# EtherIOv2.net
KiCad netlist of a schematic drawn in Altium Designer
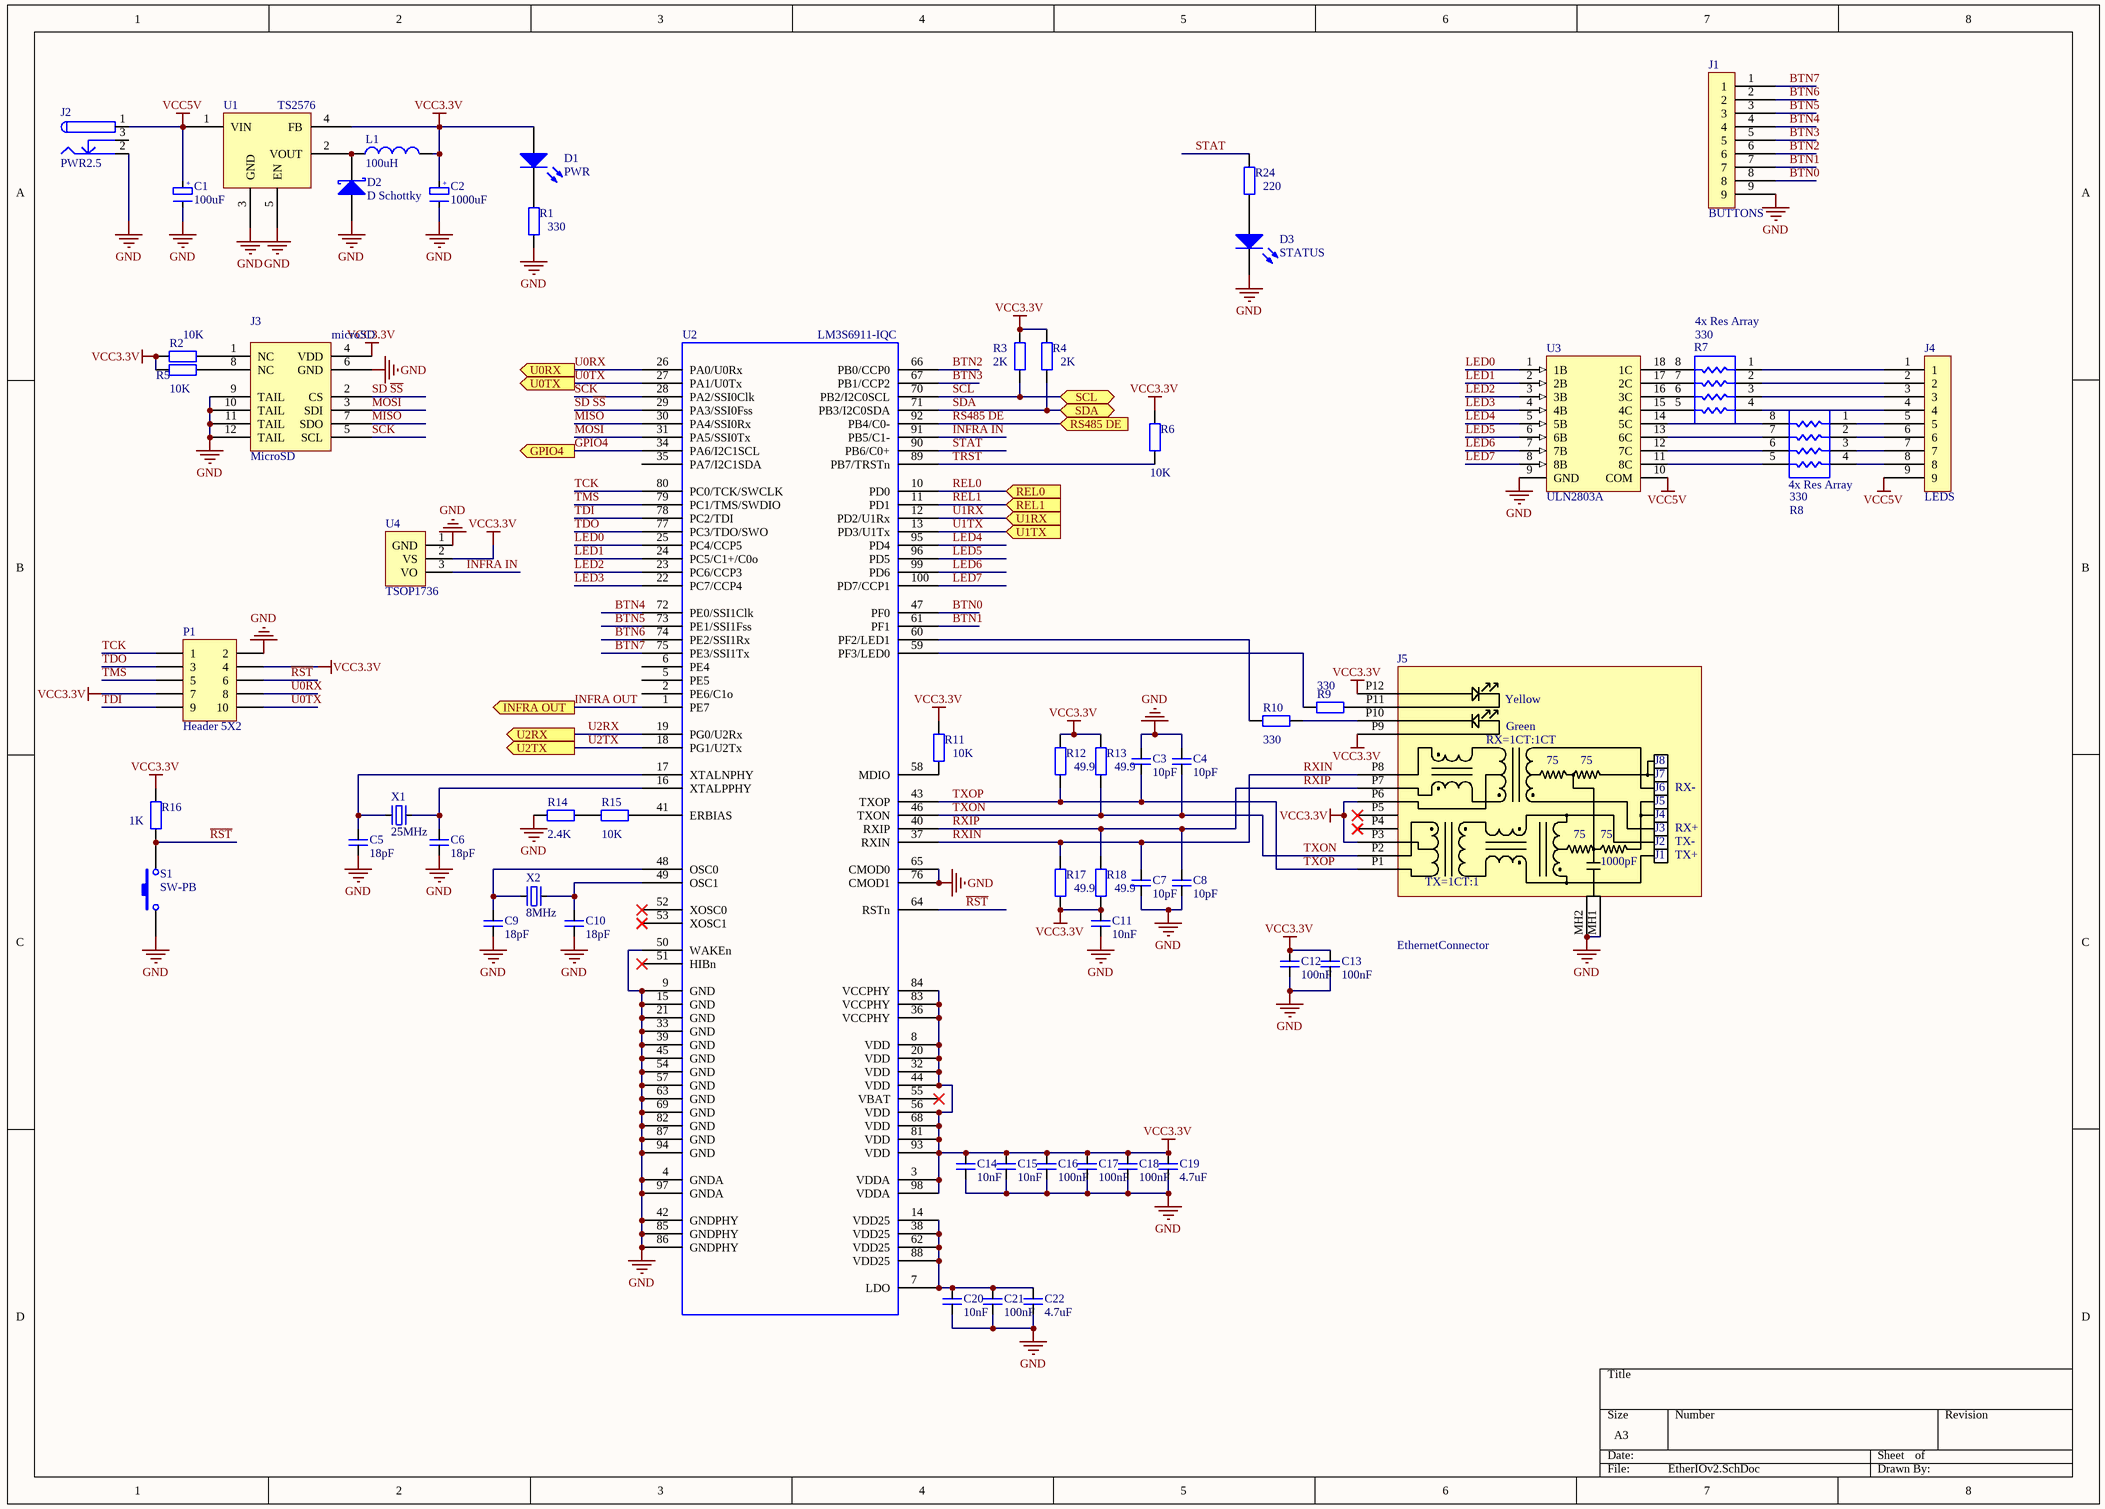
[diagram p0: EtherIOv2.SchDoc]

(export (version "E")
  (design (tool "Eeschema 10.0.6"))
  (components
    (comp (ref "C1")
      (value "100uF")
      (footprint "Electrolit Cap F80")
      (description "SMD Electrolit Capacitor")
      (fields (field (name "Comment") "100uF_25V"))
      (libsource (lib "EtherIOv2") (part "100uF_25V"))
    )
    (comp (ref "C2")
      (value "1000uF")
      (footprint "Electrolit Cap J10")
      (description "SMD Electrolit Capacitor")
      (fields (field (name "Comment") "1000uF_6V3"))
      (libsource (lib "EtherIOv2") (part "1000uF_6V3"))
    )
    (comp (ref "C3")
      (value "10pF")
      (footprint "0805 CAP")
      (description "Capacitor")
      (fields (field (name "Comment") "CAP"))
      (libsource (lib "EtherIOv2") (part "CAP"))
    )
    (comp (ref "C4")
      (value "10pF")
      (footprint "0805 CAP")
      (description "Capacitor")
      (fields (field (name "Comment") "CAP"))
      (libsource (lib "EtherIOv2") (part "CAP"))
    )
    (comp (ref "C5")
      (value "18pF")
      (footprint "0805 CAP")
      (description "Capacitor")
      (fields (field (name "Comment") "CAP"))
      (libsource (lib "EtherIOv2") (part "CAP"))
    )
    (comp (ref "C6")
      (value "18pF")
      (footprint "0805 CAP")
      (description "Capacitor")
      (fields (field (name "Comment") "CAP"))
      (libsource (lib "EtherIOv2") (part "CAP"))
    )
    (comp (ref "C7")
      (value "10pF")
      (footprint "0805 CAP")
      (description "Capacitor")
      (fields (field (name "Comment") "CAP"))
      (libsource (lib "EtherIOv2") (part "CAP"))
    )
    (comp (ref "C8")
      (value "10pF")
      (footprint "0805 CAP")
      (description "Capacitor")
      (fields (field (name "Comment") "CAP"))
      (libsource (lib "EtherIOv2") (part "CAP"))
    )
    (comp (ref "C9")
      (value "18pF")
      (footprint "0805 CAP")
      (description "Capacitor")
      (fields (field (name "Comment") "CAP"))
      (libsource (lib "EtherIOv2") (part "CAP"))
    )
    (comp (ref "C10")
      (value "18pF")
      (footprint "0805 CAP")
      (description "Capacitor")
      (fields (field (name "Comment") "CAP"))
      (libsource (lib "EtherIOv2") (part "CAP"))
    )
    (comp (ref "C11")
      (value "10nF")
      (footprint "0805 CAP")
      (description "Capacitor")
      (fields (field (name "Comment") "CAP"))
      (libsource (lib "EtherIOv2") (part "CAP"))
    )
    (comp (ref "C12")
      (value "100nF")
      (footprint "0805 CAP")
      (description "Capacitor")
      (fields (field (name "Comment") "CAP"))
      (libsource (lib "EtherIOv2") (part "CAP"))
    )
    (comp (ref "C13")
      (value "100nF")
      (footprint "0805 CAP")
      (description "Capacitor")
      (fields (field (name "Comment") "CAP"))
      (libsource (lib "EtherIOv2") (part "CAP"))
    )
    (comp (ref "C14")
      (value "10nF")
      (footprint "0805 CAP")
      (description "Capacitor")
      (fields (field (name "Comment") "CAP"))
      (libsource (lib "EtherIOv2") (part "CAP"))
    )
    (comp (ref "C15")
      (value "10nF")
      (footprint "0805 CAP")
      (description "Capacitor")
      (fields (field (name "Comment") "CAP"))
      (libsource (lib "EtherIOv2") (part "CAP"))
    )
    (comp (ref "C16")
      (value "100nF")
      (footprint "0805 CAP")
      (description "Capacitor")
      (fields (field (name "Comment") "CAP"))
      (libsource (lib "EtherIOv2") (part "CAP"))
    )
    (comp (ref "C17")
      (value "100nF")
      (footprint "0805 CAP")
      (description "Capacitor")
      (fields (field (name "Comment") "CAP"))
      (libsource (lib "EtherIOv2") (part "CAP"))
    )
    (comp (ref "C18")
      (value "100nF")
      (footprint "0805 CAP")
      (description "Capacitor")
      (fields (field (name "Comment") "CAP"))
      (libsource (lib "EtherIOv2") (part "CAP"))
    )
    (comp (ref "C19")
      (value "4.7uF")
      (footprint "0805 CAP")
      (description "Capacitor")
      (fields (field (name "Comment") "CAP"))
      (libsource (lib "EtherIOv2") (part "CAP"))
    )
    (comp (ref "C20")
      (value "10nF")
      (footprint "0805 CAP")
      (description "Capacitor")
      (fields (field (name "Comment") "CAP"))
      (libsource (lib "EtherIOv2") (part "CAP"))
    )
    (comp (ref "C21")
      (value "100nF")
      (footprint "0805 CAP")
      (description "Capacitor")
      (fields (field (name "Comment") "CAP"))
      (libsource (lib "EtherIOv2") (part "CAP"))
    )
    (comp (ref "C22")
      (value "4.7uF")
      (footprint "0805 CAP")
      (description "Capacitor")
      (fields (field (name "Comment") "CAP"))
      (libsource (lib "EtherIOv2") (part "CAP"))
    )
    (comp (ref "D1")
      (value "PWR")
      (footprint "0805 LED")
      (description "Typical RED, GREEN, YELLOW, AMBER GaAs LED")
      (fields (field (name "PUBLISHER") "Altium Limited"))
      (libsource (lib "Miscellaneous Devices") (part "LED2"))
    )
    (comp (ref "D2")
      (value "D Schottky")
      (footprint "DSO-C2/X2.3")
      (description "Schottky Diode")
      (fields (field (name "PUBLISHER") "Altium Limited"))
      (libsource (lib "Miscellaneous Devices") (part "D Schottky"))
    )
    (comp (ref "D3")
      (value "STATUS")
      (footprint "LED-1")
      (description "Typical RED GaAs LED")
      (fields (field (name "PUBLISHER") "Altium Limited"))
      (libsource (lib "Miscellaneous Devices") (part "LED1"))
    )
    (comp (ref "J1")
      (value "BUTTONS")
      (footprint "Euroblock 3.5pitch 9P")
      (libsource (lib "EtherIOv2") (part "Euroblock 9P connector"))
    )
    (comp (ref "J2")
      (value "PWR2.5")
      (footprint "KLD-0202")
      (description "Low Voltage Power Supply Connector")
      (fields (field (name "PUBLISHER") "Altium Limited"))
      (libsource (lib "EtherIOv2") (part "PWR2.5"))
    )
    (comp (ref "J3") (value "MicroSD") (footprint "microSD") (libsource (lib "Waterstars") (part "MicroSD")))
    (comp (ref "J4")
      (value "LEDS")
      (footprint "Euroblock 3.5pitch 9P")
      (libsource (lib "") (part "Euroblock 9P connector_1"))
    )
    (comp (ref "J5")
      (value "EthernetConnector")
      (footprint "LU1T516-43")
      (libsource (lib "EtherIOv2") (part "EthernetConnector"))
    )
    (comp (ref "L1")
      (value "100uH")
      (footprint "INDP127127X85N")
      (description "Inductor")
      (fields (field (name "PUBLISHER") "Altium Limited"))
      (libsource (lib "Miscellaneous Devices") (part "Inductor"))
    )
    (comp (ref "P1")
      (value "Header 5X2")
      (footprint "IDC2.54-V10D")
      (description "Header, 5-Pin, Dual row")
      (fields (field (name "PUBLISHER") "Altium Limited"))
      (libsource (lib "EtherIOv2") (part "Header 5X2"))
    )
    (comp (ref "R1")
      (value "330")
      (footprint "0805 RES")
      (description "Resistor")
      (fields (field (name "Comment") "RES") (field (name "PUBLISHER") "Altium Limited"))
      (libsource (lib "") (part "RES_1"))
    )
    (comp (ref "R2")
      (value "10K")
      (footprint "0805 RES")
      (description "Resistor")
      (fields (field (name "Comment") "RES") (field (name "PUBLISHER") "Altium Limited"))
      (libsource (lib "") (part "RES_2"))
    )
    (comp (ref "R3")
      (value "2K")
      (footprint "0805 RES")
      (description "Resistor")
      (fields (field (name "Comment") "RES") (field (name "PUBLISHER") "Altium Limited"))
      (libsource (lib "") (part "RES_1"))
    )
    (comp (ref "R4")
      (value "2K")
      (footprint "0805 RES")
      (description "Resistor")
      (fields (field (name "Comment") "RES") (field (name "PUBLISHER") "Altium Limited"))
      (libsource (lib "") (part "RES_1"))
    )
    (comp (ref "R5")
      (value "10K")
      (footprint "0805 RES")
      (description "Resistor")
      (fields (field (name "Comment") "RES") (field (name "PUBLISHER") "Altium Limited"))
      (libsource (lib "") (part "RES_2"))
    )
    (comp (ref "R6")
      (value "10K")
      (footprint "0805 RES")
      (description "Resistor")
      (fields (field (name "Comment") "RES") (field (name "PUBLISHER") "Altium Limited"))
      (libsource (lib "") (part "RES_1"))
    )
    (comp (ref "R7")
      (value "4x Res Array")
      (footprint "1206 4xRES ARRAY")
      (description "Isolated Resistor Network")
      (fields (field (name "ALTIUM_VALUE") "330") (field (name "PUBLISHER") "Altium Limited"))
      (libsource (lib "EtherIOv2") (part "4x Res Array"))
    )
    (comp (ref "R8")
      (value "4x Res Array")
      (footprint "1206 4xRES ARRAY")
      (description "Isolated Resistor Network")
      (fields (field (name "ALTIUM_VALUE") "330") (field (name "PUBLISHER") "Altium Limited"))
      (libsource (lib "EtherIOv2") (part "4x Res Array"))
    )
    (comp (ref "R9")
      (value "330")
      (footprint "0805 RES")
      (description "Resistor")
      (fields (field (name "Comment") "RES") (field (name "PUBLISHER") "Altium Limited"))
      (libsource (lib "") (part "RES_3"))
    )
    (comp (ref "R10")
      (value "330")
      (footprint "0805 RES")
      (description "Resistor")
      (fields (field (name "Comment") "RES") (field (name "PUBLISHER") "Altium Limited"))
      (libsource (lib "") (part "RES_3"))
    )
    (comp (ref "R11")
      (value "10K")
      (footprint "0805 RES")
      (description "Resistor")
      (fields (field (name "Comment") "RES") (field (name "PUBLISHER") "Altium Limited"))
      (libsource (lib "") (part "RES_1"))
    )
    (comp (ref "R12")
      (value "49.9")
      (footprint "0805 RES")
      (description "Resistor")
      (fields (field (name "Comment") "RES") (field (name "PUBLISHER") "Altium Limited"))
      (libsource (lib "") (part "RES_1"))
    )
    (comp (ref "R13")
      (value "49.9")
      (footprint "0805 RES")
      (description "Resistor")
      (fields (field (name "Comment") "RES") (field (name "PUBLISHER") "Altium Limited"))
      (libsource (lib "") (part "RES_1"))
    )
    (comp (ref "R14")
      (value "2.4K")
      (footprint "0805 RES")
      (description "Resistor")
      (fields (field (name "Comment") "RES") (field (name "PUBLISHER") "Altium Limited"))
      (libsource (lib "") (part "RES_3"))
    )
    (comp (ref "R15")
      (value "10K")
      (footprint "0805 RES")
      (description "Resistor")
      (fields (field (name "Comment") "RES") (field (name "PUBLISHER") "Altium Limited"))
      (libsource (lib "") (part "RES_3"))
    )
    (comp (ref "R16")
      (value "1K")
      (footprint "0805 RES")
      (description "Resistor")
      (fields (field (name "Comment") "RES") (field (name "PUBLISHER") "Altium Limited"))
      (libsource (lib "") (part "RES_1"))
    )
    (comp (ref "R17")
      (value "49.9")
      (footprint "0805 RES")
      (description "Resistor")
      (fields (field (name "Comment") "RES") (field (name "PUBLISHER") "Altium Limited"))
      (libsource (lib "EtherIOv2") (part "RES"))
    )
    (comp (ref "R18")
      (value "49.9")
      (footprint "0805 RES")
      (description "Resistor")
      (fields (field (name "Comment") "RES") (field (name "PUBLISHER") "Altium Limited"))
      (libsource (lib "EtherIOv2") (part "RES"))
    )
    (comp (ref "R24")
      (value "220")
      (footprint "0805 RES")
      (description "Resistor")
      (fields (field (name "Comment") "RES") (field (name "PUBLISHER") "Altium Limited"))
      (libsource (lib "") (part "RES_1"))
    )
    (comp (ref "S1")
      (value "SW-PB")
      (footprint "SPST-2")
      (description "Switch")
      (fields (field (name "PUBLISHER") "Altium Limited"))
      (libsource (lib "EtherIOv2") (part "SW-PB"))
    )
    (comp (ref "U1")
      (value "TS2576")
      (footprint "TO-263-5L")
      (description "Step Down DC-DC Converter")
      (libsource (lib "EtherIOv2") (part "TS2576"))
    )
    (comp (ref "U2")
      (value "LM3S6911-IQC")
      (footprint "Luminary+Micro:QFP50P1600X1600X160-100N")
      (description "Stellaris ARM Cortex-M3 Microcontroller")
      (fields (field (name "MFG") "Luminary Micro"))
      (libsource (lib "Luminary+Micro") (part "LM3S6611-IQC"))
    )
    (comp (ref "U3")
      (value "ULN2803A")
      (footprint "SOIC127P1030X265-18N")
      (description "8xDarlington Driver")
      (libsource (lib "EtherIOv2") (part "ULN2803A"))
    )
    (comp (ref "U4")
      (value "TSOP1736")
      (footprint "TSOP17xx")
      (description "IR Receiver, 3-Pin")
      (fields (field (name "PUBLISHER") "Altium Limited"))
      (libsource (lib "EtherIOv2") (part "TSOP17xx"))
    )
    (comp (ref "X1")
      (value "25MHz")
      (footprint "CRYSTAL_LOW")
      (description "Crystal")
      (fields (field (name "Comment") "CRYSTAL"))
      (libsource (lib "EtherIOv2") (part "CRYSTAL"))
    )
    (comp (ref "X2")
      (value "8MHz")
      (footprint "CRYSTAL_LOW")
      (description "Crystal")
      (fields (field (name "Comment") "CRYSTAL"))
      (libsource (lib "EtherIOv2") (part "CRYSTAL"))
    )
  )
  (nets
    (net (code "1") (name "/BTN0") (class "Default")
      (node (ref "J1") (pin "8") (pinfunction "8_8") (pintype "passive"))
      (node (ref "U2") (pin "47") (pinfunction "PF0_47") (pintype "passive"))
    )
    (net (code "2") (name "/BTN1") (class "Default")
      (node (ref "J1") (pin "7") (pinfunction "7_7") (pintype "passive"))
      (node (ref "U2") (pin "61") (pinfunction "PF1_61") (pintype "passive"))
    )
    (net (code "3") (name "/BTN2") (class "Default")
      (node (ref "J1") (pin "6") (pinfunction "6_6") (pintype "passive"))
      (node (ref "U2") (pin "66") (pinfunction "PB0/CCP0_66") (pintype "passive"))
    )
    (net (code "4") (name "/BTN3") (class "Default")
      (node (ref "J1") (pin "5") (pinfunction "5_5") (pintype "passive"))
      (node (ref "U2") (pin "67") (pinfunction "PB1/CCP2_67") (pintype "passive"))
    )
    (net (code "5") (name "/BTN4") (class "Default")
      (node (ref "J1") (pin "4") (pinfunction "4_4") (pintype "passive"))
      (node (ref "U2") (pin "72") (pinfunction "PE0/SSI1Clk_72") (pintype "passive"))
    )
    (net (code "6") (name "/BTN5") (class "Default")
      (node (ref "J1") (pin "3") (pinfunction "3_3") (pintype "passive"))
      (node (ref "U2") (pin "73") (pinfunction "PE1/SSI1Fss_73") (pintype "passive"))
    )
    (net (code "7") (name "/BTN6") (class "Default")
      (node (ref "J1") (pin "2") (pinfunction "2_2") (pintype "passive"))
      (node (ref "U2") (pin "74") (pinfunction "PE2/SSI1Rx_74") (pintype "passive"))
    )
    (net (code "8") (name "/BTN7") (class "Default")
      (node (ref "J1") (pin "1") (pinfunction "1_1") (pintype "passive"))
      (node (ref "U2") (pin "75") (pinfunction "PE3/SSI1Tx_75") (pintype "passive"))
    )
    (net (code "9") (name "/GPIO4") (class "Default")
      (node (ref "U2") (pin "34") (pinfunction "PA6/I2C1SCL_34") (pintype "passive"))
    )
    (net (code "10") (name "/INFRA IN") (class "Default")
      (node (ref "U2") (pin "91") (pinfunction "PB5/C1-_91") (pintype "passive"))
      (node (ref "U4") (pin "3") (pinfunction "VO_3") (pintype "passive"))
    )
    (net (code "11") (name "/INFRA OUT") (class "Default")
      (node (ref "U2") (pin "1") (pinfunction "PE7_1") (pintype "passive"))
    )
    (net (code "12") (name "/LED0") (class "Default")
      (node (ref "U2") (pin "25") (pinfunction "PC4/CCP5_25") (pintype "passive"))
      (node (ref "U3") (pin "1") (pinfunction "1B_1") (pintype "input"))
    )
    (net (code "13") (name "/LED1") (class "Default")
      (node (ref "U2") (pin "24") (pinfunction "PC5/C1+/C0o_24") (pintype "passive"))
      (node (ref "U3") (pin "2") (pinfunction "2B_2") (pintype "input"))
    )
    (net (code "14") (name "/LED2") (class "Default")
      (node (ref "U2") (pin "23") (pinfunction "PC6/CCP3_23") (pintype "passive"))
      (node (ref "U3") (pin "3") (pinfunction "3B_3") (pintype "input"))
    )
    (net (code "15") (name "/LED3") (class "Default")
      (node (ref "U2") (pin "22") (pinfunction "PC7/CCP4_22") (pintype "passive"))
      (node (ref "U3") (pin "4") (pinfunction "4B_4") (pintype "input"))
    )
    (net (code "16") (name "/LED4") (class "Default")
      (node (ref "U2") (pin "95") (pinfunction "PD4_95") (pintype "passive"))
      (node (ref "U3") (pin "5") (pinfunction "5B_5") (pintype "input"))
    )
    (net (code "17") (name "/LED5") (class "Default")
      (node (ref "U2") (pin "96") (pinfunction "PD5_96") (pintype "passive"))
      (node (ref "U3") (pin "6") (pinfunction "6B_6") (pintype "input"))
    )
    (net (code "18") (name "/LED6") (class "Default")
      (node (ref "U2") (pin "99") (pinfunction "PD6_99") (pintype "passive"))
      (node (ref "U3") (pin "7") (pinfunction "7B_7") (pintype "input"))
    )
    (net (code "19") (name "/LED7") (class "Default")
      (node (ref "U2") (pin "100") (pinfunction "PD7/CCP1_100") (pintype "passive"))
      (node (ref "U3") (pin "8") (pinfunction "8B_8") (pintype "input"))
    )
    (net (code "20") (name "/MISO") (class "Default")
      (node (ref "J3") (pin "7") (pinfunction "SDO_7") (pintype "passive"))
      (node (ref "U2") (pin "30") (pinfunction "PA4/SSI0Rx_30") (pintype "passive"))
    )
    (net (code "21") (name "/MOSI") (class "Default")
      (node (ref "J3") (pin "3") (pinfunction "SDI_3") (pintype "passive"))
      (node (ref "U2") (pin "31") (pinfunction "PA5/SSI0Tx_31") (pintype "passive"))
    )
    (net (code "22") (name "/REL0") (class "Default")
      (node (ref "U2") (pin "10") (pinfunction "PD0_10") (pintype "passive"))
    )
    (net (code "23") (name "/REL1") (class "Default")
      (node (ref "U2") (pin "11") (pinfunction "PD1_11") (pintype "passive"))
    )
    (net (code "24") (name "/RS485 DE") (class "Default")
      (node (ref "U2") (pin "92") (pinfunction "PB4/C0-_92") (pintype "passive"))
    )
    (net (code "25") (name "/RXIN") (class "Default")
      (node (ref "C7") (pin "1") (pinfunction "A_1") (pintype "passive"))
      (node (ref "J5") (pin "P8") (pinfunction "P8_P8") (pintype "passive"))
      (node (ref "R17") (pin "1") (pinfunction "1_1") (pintype "passive"))
      (node (ref "U2") (pin "37") (pinfunction "RXIN_37") (pintype "passive"))
    )
    (net (code "26") (name "/RXIP") (class "Default")
      (node (ref "C8") (pin "1") (pinfunction "A_1") (pintype "passive"))
      (node (ref "J5") (pin "P7") (pinfunction "P7_P7") (pintype "passive"))
      (node (ref "R18") (pin "1") (pinfunction "1_1") (pintype "passive"))
      (node (ref "U2") (pin "40") (pinfunction "RXIP_40") (pintype "passive"))
    )
    (net (code "27") (name "/SCK") (class "Default")
      (node (ref "J3") (pin "5") (pinfunction "SCL_5") (pintype "passive"))
      (node (ref "U2") (pin "28") (pinfunction "PA2/SSI0Clk_28") (pintype "passive"))
    )
    (net (code "28") (name "/SCL") (class "Default")
      (node (ref "R3") (pin "1") (pinfunction "1_1") (pintype "passive"))
      (node (ref "U2") (pin "70") (pinfunction "PB2/I2C0SCL_70") (pintype "passive"))
    )
    (net (code "29") (name "/SD ~{SS}") (class "Default")
      (node (ref "J3") (pin "2") (pinfunction "CS_2") (pintype "passive"))
      (node (ref "U2") (pin "29") (pinfunction "PA3/SSI0Fss_29") (pintype "passive"))
    )
    (net (code "30") (name "/SDA") (class "Default")
      (node (ref "R4") (pin "1") (pinfunction "1_1") (pintype "passive"))
      (node (ref "U2") (pin "71") (pinfunction "PB3/I2C0SDA_71") (pintype "passive"))
    )
    (net (code "31") (name "/STAT") (class "Default")
      (node (ref "R24") (pin "2") (pinfunction "2_2") (pintype "passive"))
      (node (ref "U2") (pin "90") (pinfunction "PB6/C0+_90") (pintype "passive"))
    )
    (net (code "32") (name "/TCK") (class "Default")
      (node (ref "P1") (pin "1") (pinfunction "1_1") (pintype "passive"))
      (node (ref "U2") (pin "80") (pinfunction "PC0/TCK/SWCLK_80") (pintype "passive"))
    )
    (net (code "33") (name "/TDI") (class "Default")
      (node (ref "P1") (pin "9") (pinfunction "9_9") (pintype "passive"))
      (node (ref "U2") (pin "78") (pinfunction "PC2/TDI_78") (pintype "passive"))
    )
    (net (code "34") (name "/TDO") (class "Default")
      (node (ref "P1") (pin "3") (pinfunction "3_3") (pintype "passive"))
      (node (ref "U2") (pin "77") (pinfunction "PC3/TDO/SWO_77") (pintype "passive"))
    )
    (net (code "35") (name "/TMS") (class "Default")
      (node (ref "P1") (pin "5") (pinfunction "5_5") (pintype "passive"))
      (node (ref "U2") (pin "79") (pinfunction "PC1/TMS/SWDIO_79") (pintype "passive"))
    )
    (net (code "36") (name "/TXON") (class "Default")
      (node (ref "C4") (pin "1") (pinfunction "A_1") (pintype "passive"))
      (node (ref "J5") (pin "P2") (pinfunction "P2_P2") (pintype "passive"))
      (node (ref "R13") (pin "1") (pinfunction "1_1") (pintype "passive"))
      (node (ref "U2") (pin "46") (pinfunction "TXON_46") (pintype "passive"))
    )
    (net (code "37") (name "/TXOP") (class "Default")
      (node (ref "C3") (pin "1") (pinfunction "A_1") (pintype "passive"))
      (node (ref "J5") (pin "P1") (pinfunction "P1_P1") (pintype "passive"))
      (node (ref "R12") (pin "1") (pinfunction "1_1") (pintype "passive"))
      (node (ref "U2") (pin "43") (pinfunction "TXOP_43") (pintype "passive"))
    )
    (net (code "38") (name "/U0RX") (class "Default")
      (node (ref "P1") (pin "8") (pinfunction "8_8") (pintype "passive"))
      (node (ref "U2") (pin "26") (pinfunction "PA0/U0Rx_26") (pintype "passive"))
    )
    (net (code "39") (name "/U0TX") (class "Default")
      (node (ref "P1") (pin "10") (pinfunction "10_10") (pintype "passive"))
      (node (ref "U2") (pin "27") (pinfunction "PA1/U0Tx_27") (pintype "passive"))
    )
    (net (code "40") (name "/U1RX") (class "Default")
      (node (ref "U2") (pin "12") (pinfunction "PD2/U1Rx_12") (pintype "passive"))
    )
    (net (code "41") (name "/U1TX") (class "Default")
      (node (ref "U2") (pin "13") (pinfunction "PD3/U1Tx_13") (pintype "passive"))
    )
    (net (code "42") (name "/U2RX") (class "Default")
      (node (ref "U2") (pin "19") (pinfunction "PG0/U2Rx_19") (pintype "passive"))
    )
    (net (code "43") (name "/U2TX") (class "Default")
      (node (ref "U2") (pin "18") (pinfunction "PG1/U2Tx_18") (pintype "passive"))
    )
    (net (code "44") (name "/~{RST}") (class "Default")
      (node (ref "P1") (pin "6") (pinfunction "6_6") (pintype "passive"))
      (node (ref "R16") (pin "1") (pinfunction "1_1") (pintype "passive"))
      (node (ref "S1") (pin "2") (pinfunction "2_2") (pintype "passive"))
      (node (ref "U2") (pin "64") (pinfunction "RSTn_64") (pintype "passive"))
    )
    (net (code "45") (name "/~{TRST}") (class "Default")
      (node (ref "R6") (pin "1") (pinfunction "1_1") (pintype "passive"))
      (node (ref "U2") (pin "89") (pinfunction "PB7/TRSTn_89") (pintype "passive"))
    )
    (net (code "46") (name "GND") (class "Default")
      (node (ref "C1") (pin "1") (pinfunction "B_1") (pintype "passive"))
      (node (ref "C10") (pin "1") (pinfunction "A_1") (pintype "passive"))
      (node (ref "C11") (pin "1") (pinfunction "A_1") (pintype "passive"))
      (node (ref "C12") (pin "2") (pinfunction "B_2") (pintype "passive"))
      (node (ref "C13") (pin "2") (pinfunction "B_2") (pintype "passive"))
      (node (ref "C14") (pin "1") (pinfunction "A_1") (pintype "passive"))
      (node (ref "C15") (pin "1") (pinfunction "A_1") (pintype "passive"))
      (node (ref "C16") (pin "1") (pinfunction "A_1") (pintype "passive"))
      (node (ref "C17") (pin "1") (pinfunction "A_1") (pintype "passive"))
      (node (ref "C18") (pin "1") (pinfunction "A_1") (pintype "passive"))
      (node (ref "C19") (pin "1") (pinfunction "A_1") (pintype "passive"))
      (node (ref "C2") (pin "1") (pinfunction "B_1") (pintype "passive"))
      (node (ref "C20") (pin "1") (pinfunction "A_1") (pintype "passive"))
      (node (ref "C21") (pin "1") (pinfunction "A_1") (pintype "passive"))
      (node (ref "C22") (pin "1") (pinfunction "A_1") (pintype "passive"))
      (node (ref "C3") (pin "2") (pinfunction "B_2") (pintype "passive"))
      (node (ref "C4") (pin "2") (pinfunction "B_2") (pintype "passive"))
      (node (ref "C5") (pin "1") (pinfunction "A_1") (pintype "passive"))
      (node (ref "C6") (pin "1") (pinfunction "A_1") (pintype "passive"))
      (node (ref "C7") (pin "2") (pinfunction "B_2") (pintype "passive"))
      (node (ref "C8") (pin "2") (pinfunction "B_2") (pintype "passive"))
      (node (ref "C9") (pin "1") (pinfunction "A_1") (pintype "passive"))
      (node (ref "D2") (pin "1") (pinfunction "A_1") (pintype "passive"))
      (node (ref "D3") (pin "2") (pinfunction "K_2") (pintype "passive"))
      (node (ref "J1") (pin "9") (pinfunction "9_9") (pintype "passive"))
      (node (ref "J2") (pin "2") (pinfunction "2_2") (pintype "passive"))
      (node (ref "J3") (pin "10") (pinfunction "TAIL_10") (pintype "passive"))
      (node (ref "J3") (pin "11") (pinfunction "TAIL_11") (pintype "passive"))
      (node (ref "J3") (pin "12") (pinfunction "TAIL_12") (pintype "passive"))
      (node (ref "J3") (pin "6") (pinfunction "GND_6") (pintype "passive"))
      (node (ref "J3") (pin "9") (pinfunction "TAIL_9") (pintype "passive"))
      (node (ref "J5") (pin "MH1") (pinfunction "SHIELD_MH1") (pintype "passive"))
      (node (ref "J5") (pin "MH2") (pinfunction "SHIELD_MH2") (pintype "passive"))
      (node (ref "P1") (pin "2") (pinfunction "2_2") (pintype "passive"))
      (node (ref "R1") (pin "1") (pinfunction "1_1") (pintype "passive"))
      (node (ref "R14") (pin "1") (pinfunction "1_1") (pintype "passive"))
      (node (ref "S1") (pin "1") (pinfunction "1_1") (pintype "passive"))
      (node (ref "U1") (pin "3") (pinfunction "GND_3") (pintype "power_in"))
      (node (ref "U1") (pin "5") (pinfunction "EN_5") (pintype "passive"))
      (node (ref "U2") (pin "15") (pinfunction "GND_15") (pintype "passive"))
      (node (ref "U2") (pin "21") (pinfunction "GND_21") (pintype "passive"))
      (node (ref "U2") (pin "33") (pinfunction "GND_33") (pintype "passive"))
      (node (ref "U2") (pin "39") (pinfunction "GND_39") (pintype "passive"))
      (node (ref "U2") (pin "4") (pinfunction "GNDA_4") (pintype "passive"))
      (node (ref "U2") (pin "42") (pinfunction "GNDPHY_42") (pintype "passive"))
      (node (ref "U2") (pin "45") (pinfunction "GND_45") (pintype "passive"))
      (node (ref "U2") (pin "50") (pinfunction "WAKEn_50") (pintype "passive"))
      (node (ref "U2") (pin "54") (pinfunction "GND_54") (pintype "passive"))
      (node (ref "U2") (pin "57") (pinfunction "GND_57") (pintype "passive"))
      (node (ref "U2") (pin "63") (pinfunction "GND_63") (pintype "passive"))
      (node (ref "U2") (pin "65") (pinfunction "CMOD0_65") (pintype "passive"))
      (node (ref "U2") (pin "69") (pinfunction "GND_69") (pintype "passive"))
      (node (ref "U2") (pin "76") (pinfunction "CMOD1_76") (pintype "passive"))
      (node (ref "U2") (pin "82") (pinfunction "GND_82") (pintype "passive"))
      (node (ref "U2") (pin "85") (pinfunction "GNDPHY_85") (pintype "passive"))
      (node (ref "U2") (pin "86") (pinfunction "GNDPHY_86") (pintype "passive"))
      (node (ref "U2") (pin "87") (pinfunction "GND_87") (pintype "passive"))
      (node (ref "U2") (pin "9") (pinfunction "GND_9") (pintype "passive"))
      (node (ref "U2") (pin "94") (pinfunction "GND_94") (pintype "passive"))
      (node (ref "U2") (pin "97") (pinfunction "GNDA_97") (pintype "passive"))
      (node (ref "U3") (pin "9") (pinfunction "GND_9") (pintype "power_in"))
      (node (ref "U4") (pin "1") (pinfunction "GND_1") (pintype "passive"))
    )
    (net (code "47") (name "Net-(C5-B)") (class "Default")
      (node (ref "C5") (pin "2") (pinfunction "B_2") (pintype "passive"))
      (node (ref "U2") (pin "17") (pinfunction "XTALNPHY_17") (pintype "passive"))
      (node (ref "X1") (pin "1") (pinfunction "A_1") (pintype "passive"))
    )
    (net (code "48") (name "Net-(C6-B)") (class "Default")
      (node (ref "C6") (pin "2") (pinfunction "B_2") (pintype "passive"))
      (node (ref "U2") (pin "16") (pinfunction "XTALPPHY_16") (pintype "passive"))
      (node (ref "X1") (pin "2") (pinfunction "B_2") (pintype "passive"))
    )
    (net (code "49") (name "Net-(C9-B)") (class "Default")
      (node (ref "C9") (pin "2") (pinfunction "B_2") (pintype "passive"))
      (node (ref "U2") (pin "48") (pinfunction "OSC0_48") (pintype "passive"))
      (node (ref "X2") (pin "1") (pinfunction "A_1") (pintype "passive"))
    )
    (net (code "50") (name "Net-(C10-B)") (class "Default")
      (node (ref "C10") (pin "2") (pinfunction "B_2") (pintype "passive"))
      (node (ref "U2") (pin "49") (pinfunction "OSC1_49") (pintype "passive"))
      (node (ref "X2") (pin "2") (pinfunction "B_2") (pintype "passive"))
    )
    (net (code "51") (name "Net-(C20-B)") (class "Default")
      (node (ref "C20") (pin "2") (pinfunction "B_2") (pintype "passive"))
      (node (ref "C21") (pin "2") (pinfunction "B_2") (pintype "passive"))
      (node (ref "C22") (pin "2") (pinfunction "B_2") (pintype "passive"))
      (node (ref "U2") (pin "14") (pinfunction "VDD25_14") (pintype "passive"))
      (node (ref "U2") (pin "38") (pinfunction "VDD25_38") (pintype "passive"))
      (node (ref "U2") (pin "62") (pinfunction "VDD25_62") (pintype "passive"))
      (node (ref "U2") (pin "7") (pinfunction "LDO_7") (pintype "passive"))
      (node (ref "U2") (pin "88") (pinfunction "VDD25_88") (pintype "passive"))
    )
    (net (code "52") (name "Net-(D1-K)") (class "Default")
      (node (ref "D1") (pin "2") (pinfunction "K_2") (pintype "passive"))
      (node (ref "R1") (pin "2") (pinfunction "2_2") (pintype "passive"))
    )
    (net (code "53") (name "Net-(D2-K)") (class "Default")
      (node (ref "D2") (pin "2") (pinfunction "K_2") (pintype "passive"))
      (node (ref "L1") (pin "1") (pinfunction "1_1") (pintype "passive"))
      (node (ref "U1") (pin "2") (pinfunction "VOUT_2") (pintype "passive"))
    )
    (net (code "54") (name "Net-(D3-A)") (class "Default")
      (node (ref "D3") (pin "1") (pinfunction "A_1") (pintype "passive"))
      (node (ref "R24") (pin "1") (pinfunction "1_1") (pintype "passive"))
    )
    (net (code "55") (name "Net-(J3-NC-Pad1)") (class "Default")
      (node (ref "J3") (pin "1") (pinfunction "NC_1") (pintype "passive"))
      (node (ref "R2") (pin "1") (pinfunction "1_1") (pintype "passive"))
    )
    (net (code "56") (name "Net-(J3-NC-Pad8)") (class "Default")
      (node (ref "J3") (pin "8") (pinfunction "NC_8") (pintype "passive"))
      (node (ref "R5") (pin "1") (pinfunction "1_1") (pintype "passive"))
    )
    (net (code "57") (name "Net-(J4-Pad1)") (class "Default")
      (node (ref "J4") (pin "1") (pinfunction "1_1") (pintype "passive"))
      (node (ref "R7") (pin "1") (pinfunction "1_1") (pintype "passive"))
    )
    (net (code "58") (name "Net-(J4-Pad2)") (class "Default")
      (node (ref "J4") (pin "2") (pinfunction "2_2") (pintype "passive"))
      (node (ref "R7") (pin "2") (pinfunction "2_2") (pintype "passive"))
    )
    (net (code "59") (name "Net-(J4-Pad3)") (class "Default")
      (node (ref "J4") (pin "3") (pinfunction "3_3") (pintype "passive"))
      (node (ref "R7") (pin "3") (pinfunction "3_3") (pintype "passive"))
    )
    (net (code "60") (name "Net-(J4-Pad4)") (class "Default")
      (node (ref "J4") (pin "4") (pinfunction "4_4") (pintype "passive"))
      (node (ref "R7") (pin "4") (pinfunction "4_4") (pintype "passive"))
    )
    (net (code "61") (name "Net-(J4-Pad5)") (class "Default")
      (node (ref "J4") (pin "5") (pinfunction "5_5") (pintype "passive"))
      (node (ref "R8") (pin "1") (pinfunction "1_1") (pintype "passive"))
    )
    (net (code "62") (name "Net-(J4-Pad6)") (class "Default")
      (node (ref "J4") (pin "6") (pinfunction "6_6") (pintype "passive"))
      (node (ref "R8") (pin "2") (pinfunction "2_2") (pintype "passive"))
    )
    (net (code "63") (name "Net-(J4-Pad7)") (class "Default")
      (node (ref "J4") (pin "7") (pinfunction "7_7") (pintype "passive"))
      (node (ref "R8") (pin "3") (pinfunction "3_3") (pintype "passive"))
    )
    (net (code "64") (name "Net-(J4-Pad8)") (class "Default")
      (node (ref "J4") (pin "8") (pinfunction "8_8") (pintype "passive"))
      (node (ref "R8") (pin "4") (pinfunction "4_4") (pintype "passive"))
    )
    (net (code "65") (name "Net-(J5-PadP10)") (class "Default")
      (node (ref "J5") (pin "P10") (pinfunction "P10_P10") (pintype "passive"))
      (node (ref "R10") (pin "2") (pinfunction "2_2") (pintype "passive"))
    )
    (net (code "66") (name "Net-(J5-PadP11)") (class "Default")
      (node (ref "J5") (pin "P11") (pinfunction "P11_P11") (pintype "passive"))
      (node (ref "R9") (pin "2") (pinfunction "2_2") (pintype "passive"))
    )
    (net (code "67") (name "Net-(R14-Pad2)") (class "Default")
      (node (ref "R14") (pin "2") (pinfunction "2_2") (pintype "passive"))
      (node (ref "R15") (pin "1") (pinfunction "1_1") (pintype "passive"))
    )
    (net (code "68") (name "Net-(U2-ERBIAS)") (class "Default")
      (node (ref "R15") (pin "2") (pinfunction "2_2") (pintype "passive"))
      (node (ref "U2") (pin "41") (pinfunction "ERBIAS_41") (pintype "passive"))
    )
    (net (code "69") (name "Net-(U2-MDIO)") (class "Default")
      (node (ref "R11") (pin "1") (pinfunction "1_1") (pintype "passive"))
      (node (ref "U2") (pin "58") (pinfunction "MDIO_58") (pintype "passive"))
    )
    (net (code "70") (name "Net-(U2-PF2{slash}LED1)") (class "Default")
      (node (ref "R10") (pin "1") (pinfunction "1_1") (pintype "passive"))
      (node (ref "U2") (pin "60") (pinfunction "PF2/LED1_60") (pintype "passive"))
    )
    (net (code "71") (name "Net-(U2-PF3{slash}LED0)") (class "Default")
      (node (ref "R9") (pin "1") (pinfunction "1_1") (pintype "passive"))
      (node (ref "U2") (pin "59") (pinfunction "PF3/LED0_59") (pintype "passive"))
    )
    (net (code "72") (name "Net-(U3-1C)") (class "Default")
      (node (ref "R7") (pin "8") (pinfunction "8_8") (pintype "passive"))
      (node (ref "U3") (pin "18") (pinfunction "1C_18") (pintype "open_collector"))
    )
    (net (code "73") (name "Net-(U3-2C)") (class "Default")
      (node (ref "R7") (pin "7") (pinfunction "7_7") (pintype "passive"))
      (node (ref "U3") (pin "17") (pinfunction "2C_17") (pintype "open_collector"))
    )
    (net (code "74") (name "Net-(U3-3C)") (class "Default")
      (node (ref "R7") (pin "6") (pinfunction "6_6") (pintype "passive"))
      (node (ref "U3") (pin "16") (pinfunction "3C_16") (pintype "open_collector"))
    )
    (net (code "75") (name "Net-(U3-4C)") (class "Default")
      (node (ref "R7") (pin "5") (pinfunction "5_5") (pintype "passive"))
      (node (ref "U3") (pin "15") (pinfunction "4C_15") (pintype "open_collector"))
    )
    (net (code "76") (name "Net-(U3-5C)") (class "Default")
      (node (ref "R8") (pin "8") (pinfunction "8_8") (pintype "passive"))
      (node (ref "U3") (pin "14") (pinfunction "5C_14") (pintype "open_collector"))
    )
    (net (code "77") (name "Net-(U3-6C)") (class "Default")
      (node (ref "R8") (pin "7") (pinfunction "7_7") (pintype "passive"))
      (node (ref "U3") (pin "13") (pinfunction "6C_13") (pintype "open_collector"))
    )
    (net (code "78") (name "Net-(U3-7C)") (class "Default")
      (node (ref "R8") (pin "6") (pinfunction "6_6") (pintype "passive"))
      (node (ref "U3") (pin "12") (pinfunction "7C_12") (pintype "open_collector"))
    )
    (net (code "79") (name "Net-(U3-8C)") (class "Default")
      (node (ref "R8") (pin "5") (pinfunction "5_5") (pintype "passive"))
      (node (ref "U3") (pin "11") (pinfunction "8C_11") (pintype "open_collector"))
    )
    (net (code "80") (name "VCC3.3V") (class "Default")
      (node (ref "C11") (pin "2") (pinfunction "B_2") (pintype "passive"))
      (node (ref "C12") (pin "1") (pinfunction "A_1") (pintype "passive"))
      (node (ref "C13") (pin "1") (pinfunction "A_1") (pintype "passive"))
      (node (ref "C14") (pin "2") (pinfunction "B_2") (pintype "passive"))
      (node (ref "C15") (pin "2") (pinfunction "B_2") (pintype "passive"))
      (node (ref "C16") (pin "2") (pinfunction "B_2") (pintype "passive"))
      (node (ref "C17") (pin "2") (pinfunction "B_2") (pintype "passive"))
      (node (ref "C18") (pin "2") (pinfunction "B_2") (pintype "passive"))
      (node (ref "C19") (pin "2") (pinfunction "B_2") (pintype "passive"))
      (node (ref "C2") (pin "2") (pinfunction "A_2") (pintype "passive"))
      (node (ref "D1") (pin "1") (pinfunction "A_1") (pintype "passive"))
      (node (ref "J3") (pin "4") (pinfunction "VDD_4") (pintype "passive"))
      (node (ref "J5") (pin "P12") (pinfunction "P12_P12") (pintype "passive"))
      (node (ref "J5") (pin "P3") (pinfunction "P3_P3") (pintype "passive"))
      (node (ref "J5") (pin "P6") (pinfunction "P6_P6") (pintype "passive"))
      (node (ref "J5") (pin "P9") (pinfunction "P9_P9") (pintype "passive"))
      (node (ref "L1") (pin "2") (pinfunction "2_2") (pintype "passive"))
      (node (ref "P1") (pin "4") (pinfunction "4_4") (pintype "passive"))
      (node (ref "P1") (pin "7") (pinfunction "7_7") (pintype "passive"))
      (node (ref "R11") (pin "2") (pinfunction "2_2") (pintype "passive"))
      (node (ref "R12") (pin "2") (pinfunction "2_2") (pintype "passive"))
      (node (ref "R13") (pin "2") (pinfunction "2_2") (pintype "passive"))
      (node (ref "R16") (pin "2") (pinfunction "2_2") (pintype "passive"))
      (node (ref "R17") (pin "2") (pinfunction "2_2") (pintype "passive"))
      (node (ref "R18") (pin "2") (pinfunction "2_2") (pintype "passive"))
      (node (ref "R2") (pin "2") (pinfunction "2_2") (pintype "passive"))
      (node (ref "R3") (pin "2") (pinfunction "2_2") (pintype "passive"))
      (node (ref "R4") (pin "2") (pinfunction "2_2") (pintype "passive"))
      (node (ref "R5") (pin "2") (pinfunction "2_2") (pintype "passive"))
      (node (ref "R6") (pin "2") (pinfunction "2_2") (pintype "passive"))
      (node (ref "U1") (pin "4") (pinfunction "FB_4") (pintype "passive"))
      (node (ref "U2") (pin "20") (pinfunction "VDD_20") (pintype "passive"))
      (node (ref "U2") (pin "3") (pinfunction "VDDA_3") (pintype "passive"))
      (node (ref "U2") (pin "32") (pinfunction "VDD_32") (pintype "passive"))
      (node (ref "U2") (pin "36") (pinfunction "VCCPHY_36") (pintype "passive"))
      (node (ref "U2") (pin "44") (pinfunction "VDD_44") (pintype "passive"))
      (node (ref "U2") (pin "56") (pinfunction "VDD_56") (pintype "passive"))
      (node (ref "U2") (pin "68") (pinfunction "VDD_68") (pintype "passive"))
      (node (ref "U2") (pin "8") (pinfunction "VDD_8") (pintype "passive"))
      (node (ref "U2") (pin "81") (pinfunction "VDD_81") (pintype "passive"))
      (node (ref "U2") (pin "83") (pinfunction "VCCPHY_83") (pintype "passive"))
      (node (ref "U2") (pin "84") (pinfunction "VCCPHY_84") (pintype "passive"))
      (node (ref "U2") (pin "93") (pinfunction "VDD_93") (pintype "passive"))
      (node (ref "U2") (pin "98") (pinfunction "VDDA_98") (pintype "passive"))
      (node (ref "U4") (pin "2") (pinfunction "VS_2") (pintype "passive"))
    )
    (net (code "81") (name "VCC5V") (class "Default")
      (node (ref "C1") (pin "2") (pinfunction "A_2") (pintype "passive"))
      (node (ref "J2") (pin "1") (pinfunction "1_1") (pintype "passive"))
      (node (ref "J4") (pin "9") (pinfunction "9_9") (pintype "passive"))
      (node (ref "U1") (pin "1") (pinfunction "VIN_1") (pintype "power_in"))
      (node (ref "U3") (pin "10") (pinfunction "COM_10") (pintype "power_in"))
    )
    (net (code "82") (name "unconnected-(J2-Pad3)") (class "Default")
      (node (ref "J2") (pin "3") (pinfunction "3_3") (pintype "passive"))
    )
    (net (code "83") (name "unconnected-(J5-PadP4)") (class "Default")
      (node (ref "J5") (pin "P4") (pinfunction "P4_P4") (pintype "passive+no_connect"))
    )
    (net (code "84") (name "unconnected-(J5-PadP5)") (class "Default")
      (node (ref "J5") (pin "P5") (pinfunction "P5_P5") (pintype "passive+no_connect"))
    )
    (net (code "85") (name "unconnected-(U2-HIBn-Pad51)") (class "Default")
      (node (ref "U2") (pin "51") (pinfunction "HIBn_51") (pintype "passive+no_connect"))
    )
    (net (code "86") (name "unconnected-(U2-PA7{slash}I2C1SDA-Pad35)") (class "Default")
      (node (ref "U2") (pin "35") (pinfunction "PA7/I2C1SDA_35") (pintype "passive"))
    )
    (net (code "87") (name "unconnected-(U2-PE4-Pad6)") (class "Default")
      (node (ref "U2") (pin "6") (pinfunction "PE4_6") (pintype "passive"))
    )
    (net (code "88") (name "unconnected-(U2-PE5-Pad5)") (class "Default")
      (node (ref "U2") (pin "5") (pinfunction "PE5_5") (pintype "passive"))
    )
    (net (code "89") (name "unconnected-(U2-PE6{slash}C1o-Pad2)") (class "Default")
      (node (ref "U2") (pin "2") (pinfunction "PE6/C1o_2") (pintype "passive"))
    )
    (net (code "90") (name "unconnected-(U2-VBAT-Pad55)") (class "Default")
      (node (ref "U2") (pin "55") (pinfunction "VBAT_55") (pintype "passive+no_connect"))
    )
    (net (code "91") (name "unconnected-(U2-XOSC0-Pad52)") (class "Default")
      (node (ref "U2") (pin "52") (pinfunction "XOSC0_52") (pintype "passive+no_connect"))
    )
    (net (code "92") (name "unconnected-(U2-XOSC1-Pad53)") (class "Default")
      (node (ref "U2") (pin "53") (pinfunction "XOSC1_53") (pintype "passive+no_connect"))
    )
  )
)
